# ESP8266ProgrammeBoard.net
KiCad netlist of a schematic drawn in Altium Designer
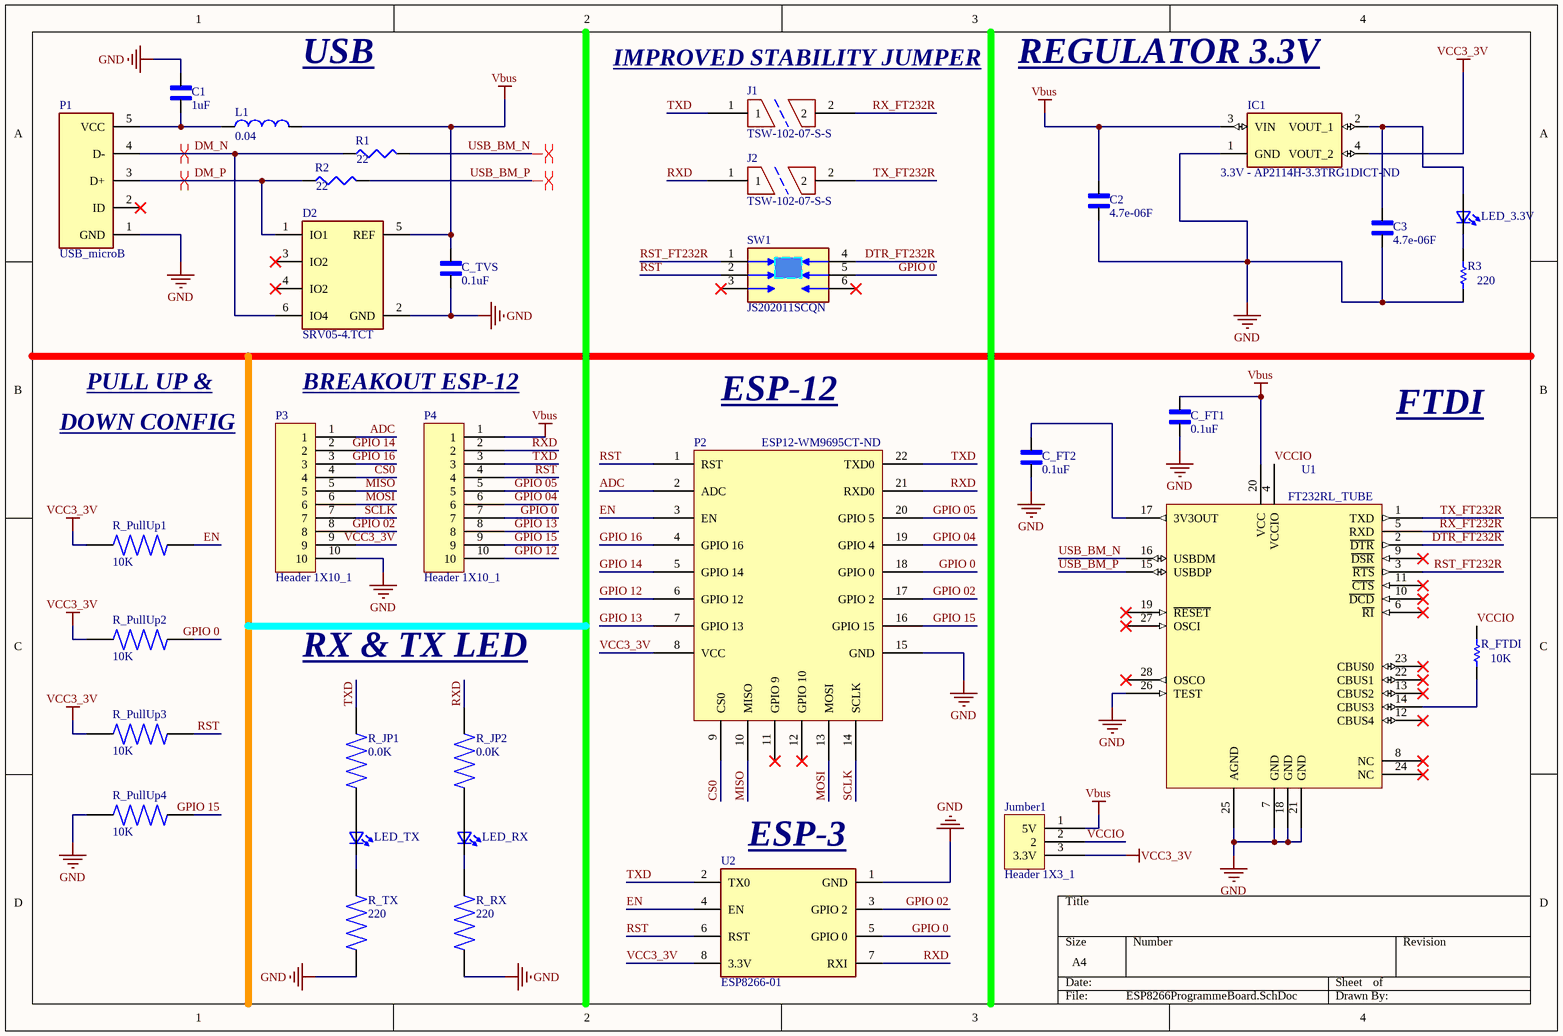
[diagram p0: ESP8266ProgrammeBoard.SchDoc]

(export (version "E")
  (design (tool "Eeschema 10.0.6"))
  (components
    (comp (ref "C1")
      (value "1uF")
      (footprint "0805Y0500104JXT:CAPC2012X130N")
      (fields (field (name "MF") "{'manufacturer': u'Syfer'}") (field (name "MP") "0805Y0500104JXT"))
      (libsource (lib "*") (part "0805Y0500104JXT"))
    )
    (comp (ref "C2")
      (value "4.7e-06F")
      (footprint "0805Y0500104JXT:CAPC2012X130N")
      (fields (field (name "MF") "{'manufacturer': u'Syfer'}") (field (name "MP") "0805Y0500104JXT"))
      (libsource (lib "*") (part "0805Y0500104JXT"))
    )
    (comp (ref "C3")
      (value "4.7e-06F")
      (footprint "0805Y0500104JXT:CAPC2012X130N")
      (fields (field (name "MF") "{'manufacturer': u'Syfer'}") (field (name "MP") "0805Y0500104JXT"))
      (libsource (lib "*") (part "0805Y0500104JXT"))
    )
    (comp (ref "C_FT1")
      (value "0.1uF")
      (footprint "0805Y0500104JXT:CAPC2012X130N")
      (fields (field (name "MF") "{'manufacturer': u'Syfer'}") (field (name "MP") "0805Y0500104JXT"))
      (libsource (lib "*") (part "0805Y0500104JXT"))
    )
    (comp (ref "C_FT2")
      (value "0.1uF")
      (footprint "0805Y0500104JXT:CAPC2012X130N")
      (fields (field (name "MF") "{'manufacturer': u'Syfer'}") (field (name "MP") "0805Y0500104JXT"))
      (libsource (lib "*") (part "0805Y0500104JXT"))
    )
    (comp (ref "C_TVS")
      (value "0.1uF")
      (footprint "0805Y0500104JXT:CAPC2012X130N")
      (fields (field (name "MF") "{'manufacturer': u'Syfer'}") (field (name "MP") "0805Y0500104JXT"))
      (libsource (lib "*") (part "0805Y0500104JXT"))
    )
    (comp (ref "D2")
      (value "SRV05-4.TCT")
      (footprint "SRV05-4.TCT")
      (description "Semtech SRV05-4.TCT, Uni-Directional TVS Diode Array, 300W, 6-Pin SOT-23")
      (libsource (lib "AlaHassine") (part "SRV05-4.TCT"))
    )
    (comp (ref "IC1")
      (value "3.3V - AP2114H-3.3TRG1DICT-ND")
      (footprint "AP2114H-3.3TRG1")
      (description "Voltage Regulators, LDO, 1.5MHz CMOS LDO 2.5V to 5V 600mV ¦ Diodes Inc AP2114H-3.3TRG1")
      (libsource (lib "AlaHassine") (part "AP2114H-3.3TRG1"))
    )
    (comp (ref "J1")
      (value "TSW-102-07-S-S")
      (footprint "TSW-102-07-S-S")
      (description "CONN HEADER 2POS .100\" SGL GOLD")
      (libsource (lib "AlaHassine") (part "TSW-102-07-S-S"))
    )
    (comp (ref "J2")
      (value "TSW-102-07-S-S")
      (footprint "TSW-102-07-S-S")
      (description "CONN HEADER 2POS .100\" SGL GOLD")
      (libsource (lib "AlaHassine") (part "TSW-102-07-S-S"))
    )
    (comp (ref "Jumber1")
      (value "Header 1X3_1")
      (footprint "Header 1X3_1")
      (libsource (lib "AlaHassine") (part "Header 1X3_1"))
    )
    (comp (ref "L1")
      (value "0.04")
      (footprint "742792601:WE-CBF_0603_W2.6")
      (fields (field (name "MF") "{'manufacturer': u'Wurth Electronics'}") (field (name "MP") "742792601"))
      (libsource (lib "*") (part "WE-CBF_0603"))
    )
    (comp (ref "LED_3.3V")
      (value "LTST-C191KRKT")
      (footprint "0603")
      (description "http://octopart.com/ltst-c190krkt-lite-on-549893")
      (libsource (lib "LTST-C191KRKT") (part "LTST-C191KRKT"))
    )
    (comp (ref "LED_RX")
      (value "LTST-C191KRKT")
      (footprint "0603")
      (description "http://octopart.com/ltst-c190krkt-lite-on-549893")
      (libsource (lib "LTST-C191KRKT") (part "LTST-C191KRKT"))
    )
    (comp (ref "LED_TX")
      (value "LTST-C191KRKT")
      (footprint "0603")
      (description "http://octopart.com/ltst-c190krkt-lite-on-549893")
      (libsource (lib "LTST-C191KRKT") (part "LTST-C191KRKT"))
    )
    (comp (ref "P1")
      (value "USB_microB")
      (footprint "Reversed_USB_microB")
      (description "USB - micro B USB 2.0 Receptacle Connector 5 Position Surface Mount, Right Angle; Through Hole")
      (libsource (lib "AlaHassine") (part "Reversed_USB_microB"))
    )
    (comp (ref "P2")
      (value "ESP12-WM9695CT-ND")
      (footprint "ESP8266-ESP12")
      (libsource (lib "AlaHassine") (part "ESP12-WM9695CT-ND"))
    )
    (comp (ref "P3")
      (value "Header 1X10_1")
      (footprint "Header 1X10_1")
      (libsource (lib "AlaHassine") (part "Header 1X10_1"))
    )
    (comp (ref "P4")
      (value "Header 1X10_1")
      (footprint "Header 1X10_1")
      (libsource (lib "AlaHassine") (part "Header 1X10_1"))
    )
    (comp (ref "R1")
      (value "22")
      (footprint "J1-0603")
      (description "Resistor")
      (fields (field (name "Comment") "Res3") (field (name "PUBLISHER") "Altium Limited"))
      (libsource (lib "Miscellaneous Devices") (part "Res3"))
    )
    (comp (ref "R2")
      (value "22")
      (footprint "J1-0603")
      (description "Resistor")
      (fields (field (name "Comment") "Res3") (field (name "PUBLISHER") "Altium Limited"))
      (libsource (lib "Miscellaneous Devices") (part "Res3"))
    )
    (comp (ref "R3")
      (value "220")
      (footprint "RESC1608X55N")
      (description "Resistor")
      (fields (field (name "Comment") "Res1") (field (name "PUBLISHER") "Altium Limited"))
      (libsource (lib "Miscellaneous Devices") (part "Res1"))
    )
    (comp (ref "R_FTDI")
      (value "10K")
      (footprint "RESC1608X55N")
      (description "Resistor")
      (fields (field (name "Comment") "Res1") (field (name "PUBLISHER") "Altium Limited"))
      (libsource (lib "Miscellaneous Devices") (part "Res1"))
    )
    (comp (ref "R_JP1")
      (value "0.0K")
      (footprint "RK73G1JTTD1002F:RESC1608X55N")
      (fields (field (name "MF") "{'manufacturer': u'KOA Speer'}") (field (name "MP") "RK73G1JTTD1002F"))
      (libsource (lib "*") (part "RK73G1JTTD1002F"))
    )
    (comp (ref "R_JP2")
      (value "0.0K")
      (footprint "RK73G1JTTD1002F:RESC1608X55N")
      (fields (field (name "MF") "{'manufacturer': u'KOA Speer'}") (field (name "MP") "RK73G1JTTD1002F"))
      (libsource (lib "*") (part "RK73G1JTTD1002F"))
    )
    (comp (ref "R_PullUp1")
      (value "10K")
      (footprint "RK73G1JTTD1002F:RESC1608X55N")
      (fields (field (name "MF") "{'manufacturer': u'KOA Speer'}") (field (name "MP") "RK73G1JTTD1002F"))
      (libsource (lib "*") (part "RK73G1JTTD1002F"))
    )
    (comp (ref "R_PullUp2")
      (value "10K")
      (footprint "RK73G1JTTD1002F:RESC1608X55N")
      (fields (field (name "MF") "{'manufacturer': u'KOA Speer'}") (field (name "MP") "RK73G1JTTD1002F"))
      (libsource (lib "*") (part "RK73G1JTTD1002F"))
    )
    (comp (ref "R_PullUp3")
      (value "10K")
      (footprint "RK73G1JTTD1002F:RESC1608X55N")
      (fields (field (name "MF") "{'manufacturer': u'KOA Speer'}") (field (name "MP") "RK73G1JTTD1002F"))
      (libsource (lib "*") (part "RK73G1JTTD1002F"))
    )
    (comp (ref "R_PullUp4")
      (value "10K")
      (footprint "RK73G1JTTD1002F:RESC1608X55N")
      (fields (field (name "MF") "{'manufacturer': u'KOA Speer'}") (field (name "MP") "RK73G1JTTD1002F"))
      (libsource (lib "*") (part "RK73G1JTTD1002F"))
    )
    (comp (ref "R_RX")
      (value "220")
      (footprint "RK73G1JTTD1002F:RESC1608X55N")
      (fields (field (name "MF") "{'manufacturer': u'KOA Speer'}") (field (name "MP") "RK73G1JTTD1002F"))
      (libsource (lib "*") (part "RK73G1JTTD1002F"))
    )
    (comp (ref "R_TX")
      (value "220")
      (footprint "RESC1608X55N")
      (fields (field (name "MF") "{'manufacturer': u'KOA Speer'}") (field (name "MP") "RK73G1JTTD1002F"))
      (libsource (lib "*") (part "RK73G1JTTD1002F"))
    )
    (comp (ref "SW1")
      (value "JS202011SCQN")
      (footprint "SW_JS202011SCQN")
      (libsource (lib "AlaHassine") (part "JS202011SCQN"))
    )
    (comp (ref "U1")
      (value "FT232RL_TUBE")
      (footprint "FT232RL_TUBE")
      (description "FT232RL-Tube\r\nUSB UART Asynchronous Serial Data Transfer Chip, 28-pin SSOP, Tube")
      (libsource (lib "AlaHassine") (part "FT232RL_TUBE"))
    )
    (comp (ref "U2")
      (value "ESP8266-01")
      (footprint "ESP8266-01/ESP-01")
      (libsource (lib "AlaHassine") (part "ESP8266-01_ESP-01"))
    )
  )
  (nets
    (net (code "1") (name "/ADC") (class "Default")
      (node (ref "P2") (pin "2") (pinfunction "ADC_2") (pintype "passive"))
      (node (ref "P3") (pin "1") (pinfunction "1_1") (pintype "passive"))
    )
    (net (code "2") (name "/CS0") (class "Default")
      (node (ref "P2") (pin "9") (pinfunction "CS0_9") (pintype "passive"))
      (node (ref "P3") (pin "4") (pinfunction "4_4") (pintype "passive"))
    )
    (net (code "3") (name "/DM_N") (class "Default")
      (node (ref "D2") (pin "6") (pinfunction "IO4_6") (pintype "passive"))
      (node (ref "P1") (pin "4") (pinfunction "D-_4") (pintype "passive"))
      (node (ref "R1") (pin "1") (pinfunction "1_1") (pintype "passive"))
    )
    (net (code "4") (name "/DM_P") (class "Default")
      (node (ref "D2") (pin "1") (pinfunction "IO1_1") (pintype "passive"))
      (node (ref "P1") (pin "3") (pinfunction "D+_3") (pintype "passive"))
      (node (ref "R2") (pin "1") (pinfunction "1_1") (pintype "passive"))
    )
    (net (code "5") (name "/DTR_FT232R") (class "Default")
      (node (ref "SW1") (pin "4") (pinfunction "4_4") (pintype "passive"))
      (node (ref "U1") (pin "2") (pinfunction "~{DTR}_2") (pintype "output"))
    )
    (net (code "6") (name "/EN") (class "Default")
      (node (ref "P2") (pin "3") (pinfunction "EN_3") (pintype "passive"))
      (node (ref "R_PullUp1") (pin "2") (pinfunction "2_2") (pintype "passive"))
      (node (ref "U2") (pin "4") (pinfunction "EN_4") (pintype "passive"))
    )
    (net (code "7") (name "/GPIO 0") (class "Default")
      (node (ref "P2") (pin "18") (pinfunction "GPIO_0_18") (pintype "passive"))
      (node (ref "P4") (pin "7") (pinfunction "7_7") (pintype "passive"))
      (node (ref "R_PullUp2") (pin "2") (pinfunction "2_2") (pintype "passive"))
      (node (ref "SW1") (pin "5") (pinfunction "5_5") (pintype "passive"))
      (node (ref "U2") (pin "5") (pinfunction "GPIO_0_5") (pintype "passive"))
    )
    (net (code "8") (name "/GPIO 02") (class "Default")
      (node (ref "P2") (pin "17") (pinfunction "GPIO_2_17") (pintype "passive"))
      (node (ref "P3") (pin "8") (pinfunction "8_8") (pintype "passive"))
      (node (ref "U2") (pin "3") (pinfunction "GPIO_2_3") (pintype "passive"))
    )
    (net (code "9") (name "/GPIO 04") (class "Default")
      (node (ref "P2") (pin "19") (pinfunction "GPIO_4_19") (pintype "passive"))
      (node (ref "P4") (pin "6") (pinfunction "6_6") (pintype "passive"))
    )
    (net (code "10") (name "/GPIO 05") (class "Default")
      (node (ref "P2") (pin "20") (pinfunction "GPIO_5_20") (pintype "passive"))
      (node (ref "P4") (pin "5") (pinfunction "5_5") (pintype "passive"))
    )
    (net (code "11") (name "/GPIO 12") (class "Default")
      (node (ref "P2") (pin "6") (pinfunction "GPIO_12_6") (pintype "passive"))
      (node (ref "P4") (pin "10") (pinfunction "10_10") (pintype "passive"))
    )
    (net (code "12") (name "/GPIO 13") (class "Default")
      (node (ref "P2") (pin "7") (pinfunction "GPIO_13_7") (pintype "passive"))
      (node (ref "P4") (pin "8") (pinfunction "8_8") (pintype "passive"))
    )
    (net (code "13") (name "/GPIO 14") (class "Default")
      (node (ref "P2") (pin "5") (pinfunction "GPIO_14_5") (pintype "passive"))
      (node (ref "P3") (pin "2") (pinfunction "2_2") (pintype "passive"))
    )
    (net (code "14") (name "/GPIO 15") (class "Default")
      (node (ref "P2") (pin "16") (pinfunction "GPIO_15_16") (pintype "passive"))
      (node (ref "P4") (pin "9") (pinfunction "9_9") (pintype "passive"))
      (node (ref "R_PullUp4") (pin "2") (pinfunction "2_2") (pintype "passive"))
    )
    (net (code "15") (name "/GPIO 16") (class "Default")
      (node (ref "P2") (pin "4") (pinfunction "GPIO_16_4") (pintype "passive"))
      (node (ref "P3") (pin "3") (pinfunction "3_3") (pintype "passive"))
    )
    (net (code "16") (name "/MISO") (class "Default")
      (node (ref "P2") (pin "10") (pinfunction "MISO_10") (pintype "passive"))
      (node (ref "P3") (pin "5") (pinfunction "5_5") (pintype "passive"))
    )
    (net (code "17") (name "/MOSI") (class "Default")
      (node (ref "P2") (pin "13") (pinfunction "MOSI_13") (pintype "passive"))
      (node (ref "P3") (pin "6") (pinfunction "6_6") (pintype "passive"))
    )
    (net (code "18") (name "/RST") (class "Default")
      (node (ref "P2") (pin "1") (pinfunction "RST_1") (pintype "passive"))
      (node (ref "P4") (pin "4") (pinfunction "4_4") (pintype "passive"))
      (node (ref "R_PullUp3") (pin "2") (pinfunction "2_2") (pintype "passive"))
      (node (ref "SW1") (pin "2") (pinfunction "2_2") (pintype "passive"))
      (node (ref "U2") (pin "6") (pinfunction "RST_6") (pintype "passive"))
    )
    (net (code "19") (name "/RST_FT232R") (class "Default")
      (node (ref "SW1") (pin "1") (pinfunction "1_1") (pintype "passive"))
      (node (ref "U1") (pin "3") (pinfunction "~{RTS}_3") (pintype "output"))
    )
    (net (code "20") (name "/RXD") (class "Default")
      (node (ref "J2") (pin "1") (pinfunction "1_1") (pintype "passive"))
      (node (ref "P2") (pin "21") (pinfunction "RXD0_21") (pintype "passive"))
      (node (ref "P4") (pin "2") (pinfunction "2_2") (pintype "passive"))
      (node (ref "R_JP2") (pin "2") (pinfunction "2_2") (pintype "passive"))
      (node (ref "U2") (pin "7") (pinfunction "RXI_7") (pintype "power_in"))
    )
    (net (code "21") (name "/RX_FT232R") (class "Default")
      (node (ref "J1") (pin "2") (pinfunction "2_2") (pintype "passive"))
      (node (ref "U1") (pin "5") (pinfunction "RXD_5") (pintype "passive"))
    )
    (net (code "22") (name "/SCLK") (class "Default")
      (node (ref "P2") (pin "14") (pinfunction "SCLK_14") (pintype "passive"))
      (node (ref "P3") (pin "7") (pinfunction "7_7") (pintype "passive"))
    )
    (net (code "23") (name "/TXD") (class "Default")
      (node (ref "J1") (pin "1") (pinfunction "1_1") (pintype "passive"))
      (node (ref "P2") (pin "22") (pinfunction "TXD0_22") (pintype "passive"))
      (node (ref "P4") (pin "3") (pinfunction "3_3") (pintype "passive"))
      (node (ref "R_JP1") (pin "2") (pinfunction "2_2") (pintype "passive"))
      (node (ref "U2") (pin "2") (pinfunction "TX0_2") (pintype "passive"))
    )
    (net (code "24") (name "/TX_FT232R") (class "Default")
      (node (ref "J2") (pin "2") (pinfunction "2_2") (pintype "passive"))
      (node (ref "U1") (pin "1") (pinfunction "TXD_1") (pintype "output"))
    )
    (net (code "25") (name "/USB_BM_N") (class "Default")
      (node (ref "R1") (pin "2") (pinfunction "2_2") (pintype "passive"))
      (node (ref "U1") (pin "16") (pinfunction "USBDM_16") (pintype "bidirectional"))
    )
    (net (code "26") (name "/USB_BM_P") (class "Default")
      (node (ref "R2") (pin "2") (pinfunction "2_2") (pintype "passive"))
      (node (ref "U1") (pin "15") (pinfunction "USBDP_15") (pintype "bidirectional"))
    )
    (net (code "27") (name "/VCCIO") (class "Default")
      (node (ref "Jumber1") (pin "2") (pinfunction "2_2") (pintype "passive"))
      (node (ref "R_FTDI") (pin "2") (pinfunction "2_2") (pintype "passive"))
      (node (ref "U1") (pin "4") (pinfunction "VCCIO_4") (pintype "passive"))
    )
    (net (code "28") (name "GND") (class "Default")
      (node (ref "C1") (pin "2") (pinfunction "2_2") (pintype "passive"))
      (node (ref "C2") (pin "1") (pinfunction "1_1") (pintype "passive"))
      (node (ref "C3") (pin "1") (pinfunction "1_1") (pintype "passive"))
      (node (ref "C_FT1") (pin "1") (pinfunction "1_1") (pintype "passive"))
      (node (ref "C_FT2") (pin "1") (pinfunction "1_1") (pintype "passive"))
      (node (ref "C_TVS") (pin "1") (pinfunction "1_1") (pintype "passive"))
      (node (ref "D2") (pin "2") (pinfunction "GND_2") (pintype "passive"))
      (node (ref "IC1") (pin "1") (pinfunction "GND_1") (pintype "passive"))
      (node (ref "P1") (pin "1") (pinfunction "GND_1") (pintype "passive"))
      (node (ref "P2") (pin "15") (pinfunction "GND_15") (pintype "passive"))
      (node (ref "P3") (pin "10") (pinfunction "10_10") (pintype "passive"))
      (node (ref "R3") (pin "1") (pinfunction "1_1") (pintype "passive"))
      (node (ref "R_PullUp4") (pin "1") (pinfunction "1_1") (pintype "passive"))
      (node (ref "R_RX") (pin "1") (pinfunction "1_1") (pintype "passive"))
      (node (ref "R_TX") (pin "1") (pinfunction "1_1") (pintype "passive"))
      (node (ref "U1") (pin "18") (pinfunction "GND_18") (pintype "passive"))
      (node (ref "U1") (pin "21") (pinfunction "GND_21") (pintype "passive"))
      (node (ref "U1") (pin "25") (pinfunction "AGND_25") (pintype "passive"))
      (node (ref "U1") (pin "26") (pinfunction "TEST_26") (pintype "input"))
      (node (ref "U1") (pin "7") (pinfunction "GND_7") (pintype "passive"))
      (node (ref "U2") (pin "1") (pinfunction "GND_1") (pintype "power_in"))
    )
    (net (code "29") (name "Net-(IC1-VOUT_1)") (class "Default")
      (node (ref "C3") (pin "2") (pinfunction "2_2") (pintype "passive"))
      (node (ref "IC1") (pin "2") (pinfunction "VOUT_1_2") (pintype "bidirectional"))
      (node (ref "LED_3.3V") (pin "2") (pinfunction "A2_2") (pintype "passive"))
    )
    (net (code "30") (name "Net-(LED_3.3V-K2)") (class "Default")
      (node (ref "LED_3.3V") (pin "1") (pinfunction "K2_1") (pintype "passive"))
      (node (ref "R3") (pin "2") (pinfunction "2_2") (pintype "passive"))
    )
    (net (code "31") (name "Net-(LED_RX-A2)") (class "Default")
      (node (ref "LED_RX") (pin "2") (pinfunction "A2_2") (pintype "passive"))
      (node (ref "R_JP2") (pin "1") (pinfunction "1_1") (pintype "passive"))
    )
    (net (code "32") (name "Net-(LED_RX-K2)") (class "Default")
      (node (ref "LED_RX") (pin "1") (pinfunction "K2_1") (pintype "passive"))
      (node (ref "R_RX") (pin "2") (pinfunction "2_2") (pintype "passive"))
    )
    (net (code "33") (name "Net-(LED_TX-A2)") (class "Default")
      (node (ref "LED_TX") (pin "2") (pinfunction "A2_2") (pintype "passive"))
      (node (ref "R_JP1") (pin "1") (pinfunction "1_1") (pintype "passive"))
    )
    (net (code "34") (name "Net-(LED_TX-K2)") (class "Default")
      (node (ref "LED_TX") (pin "1") (pinfunction "K2_1") (pintype "passive"))
      (node (ref "R_TX") (pin "2") (pinfunction "2_2") (pintype "passive"))
    )
    (net (code "35") (name "Net-(P1-VCC)") (class "Default")
      (node (ref "C1") (pin "1") (pinfunction "1_1") (pintype "passive"))
      (node (ref "L1") (pin "1") (pinfunction "1_1") (pintype "passive"))
      (node (ref "P1") (pin "5") (pinfunction "VCC_5") (pintype "passive"))
    )
    (net (code "36") (name "Net-(U1-3V3OUT)") (class "Default")
      (node (ref "C_FT2") (pin "2") (pinfunction "2_2") (pintype "passive"))
      (node (ref "U1") (pin "17") (pinfunction "3V3OUT_17") (pintype "output"))
    )
    (net (code "37") (name "Net-(U1-CBUS3)") (class "Default")
      (node (ref "R_FTDI") (pin "1") (pinfunction "1_1") (pintype "passive"))
      (node (ref "U1") (pin "14") (pinfunction "CBUS3_14") (pintype "bidirectional"))
    )
    (net (code "38") (name "VCC3_3V") (class "Default")
      (node (ref "IC1") (pin "4") (pinfunction "VOUT_2_4") (pintype "bidirectional"))
      (node (ref "Jumber1") (pin "3") (pinfunction "3.3V_3") (pintype "passive"))
      (node (ref "P2") (pin "8") (pinfunction "VCC_8") (pintype "passive"))
      (node (ref "P3") (pin "9") (pinfunction "9_9") (pintype "passive"))
      (node (ref "R_PullUp1") (pin "1") (pinfunction "1_1") (pintype "passive"))
      (node (ref "R_PullUp2") (pin "1") (pinfunction "1_1") (pintype "passive"))
      (node (ref "R_PullUp3") (pin "1") (pinfunction "1_1") (pintype "passive"))
      (node (ref "U2") (pin "8") (pinfunction "3.3V_8") (pintype "passive"))
    )
    (net (code "39") (name "Vbus") (class "Default")
      (node (ref "C2") (pin "2") (pinfunction "2_2") (pintype "passive"))
      (node (ref "C_FT1") (pin "2") (pinfunction "2_2") (pintype "passive"))
      (node (ref "C_TVS") (pin "2") (pinfunction "2_2") (pintype "passive"))
      (node (ref "D2") (pin "5") (pinfunction "REF_5") (pintype "passive"))
      (node (ref "IC1") (pin "3") (pinfunction "VIN_3") (pintype "bidirectional"))
      (node (ref "Jumber1") (pin "1") (pinfunction "5V_1") (pintype "passive"))
      (node (ref "L1") (pin "2") (pinfunction "2_2") (pintype "passive"))
      (node (ref "P4") (pin "1") (pinfunction "1_1") (pintype "passive"))
      (node (ref "U1") (pin "20") (pinfunction "VCC_20") (pintype "passive"))
    )
    (net (code "40") (name "unconnected-(D2-IO2-Pad3)") (class "Default")
      (node (ref "D2") (pin "3") (pinfunction "IO2_3") (pintype "passive+no_connect"))
    )
    (net (code "41") (name "unconnected-(D2-IO2-Pad4)") (class "Default")
      (node (ref "D2") (pin "4") (pinfunction "IO2_4") (pintype "passive+no_connect"))
    )
    (net (code "42") (name "unconnected-(P1-ID-Pad2)") (class "Default")
      (node (ref "P1") (pin "2") (pinfunction "ID_2") (pintype "passive+no_connect"))
    )
    (net (code "43") (name "unconnected-(P2-GPIO_9-Pad11)") (class "Default")
      (node (ref "P2") (pin "11") (pinfunction "GPIO_9_11") (pintype "passive+no_connect"))
    )
    (net (code "44") (name "unconnected-(P2-GPIO_10-Pad12)") (class "Default")
      (node (ref "P2") (pin "12") (pinfunction "GPIO_10_12") (pintype "passive+no_connect"))
    )
    (net (code "45") (name "unconnected-(SW1-Pad3)") (class "Default")
      (node (ref "SW1") (pin "3") (pinfunction "3_3") (pintype "passive+no_connect"))
    )
    (net (code "46") (name "unconnected-(SW1-Pad6)") (class "Default")
      (node (ref "SW1") (pin "6") (pinfunction "6_6") (pintype "passive+no_connect"))
    )
    (net (code "47") (name "unconnected-(U1-CBUS0-Pad23)") (class "Default")
      (node (ref "U1") (pin "23") (pinfunction "CBUS0_23") (pintype "bidirectional+no_connect"))
    )
    (net (code "48") (name "unconnected-(U1-CBUS1-Pad22)") (class "Default")
      (node (ref "U1") (pin "22") (pinfunction "CBUS1_22") (pintype "bidirectional+no_connect"))
    )
    (net (code "49") (name "unconnected-(U1-CBUS2-Pad13)") (class "Default")
      (node (ref "U1") (pin "13") (pinfunction "CBUS2_13") (pintype "bidirectional+no_connect"))
    )
    (net (code "50") (name "unconnected-(U1-CBUS4-Pad12)") (class "Default")
      (node (ref "U1") (pin "12") (pinfunction "CBUS4_12") (pintype "bidirectional+no_connect"))
    )
    (net (code "51") (name "unconnected-(U1-NC-Pad8)") (class "Default")
      (node (ref "U1") (pin "8") (pinfunction "NC_8") (pintype "passive+no_connect"))
    )
    (net (code "52") (name "unconnected-(U1-NC-Pad24)") (class "Default")
      (node (ref "U1") (pin "24") (pinfunction "NC_24") (pintype "passive+no_connect"))
    )
    (net (code "53") (name "unconnected-(U1-OSCI-Pad27)") (class "Default")
      (node (ref "U1") (pin "27") (pinfunction "OSCI_27") (pintype "input+no_connect"))
    )
    (net (code "54") (name "unconnected-(U1-OSCO-Pad28)") (class "Default")
      (node (ref "U1") (pin "28") (pinfunction "OSCO_28") (pintype "output+no_connect"))
    )
    (net (code "55") (name "unconnected-(U1-~{CTS}-Pad11)") (class "Default")
      (node (ref "U1") (pin "11") (pinfunction "~{CTS}_11") (pintype "input+no_connect"))
    )
    (net (code "56") (name "unconnected-(U1-~{DCD}-Pad10)") (class "Default")
      (node (ref "U1") (pin "10") (pinfunction "~{DCD}_10") (pintype "input+no_connect"))
    )
    (net (code "57") (name "unconnected-(U1-~{DSR}-Pad9)") (class "Default")
      (node (ref "U1") (pin "9") (pinfunction "~{DSR}_9") (pintype "input+no_connect"))
    )
    (net (code "58") (name "unconnected-(U1-~{RESET}-Pad19)") (class "Default")
      (node (ref "U1") (pin "19") (pinfunction "~{RESET}_19") (pintype "input+no_connect"))
    )
    (net (code "59") (name "unconnected-(U1-~{RI}-Pad6)") (class "Default")
      (node (ref "U1") (pin "6") (pinfunction "~{RI}_6") (pintype "input+no_connect"))
    )
  )
)
